# PSPS_AVNC_MITCH_2021-02-28.net
KiCad netlist of a schematic drawn in EAGLE
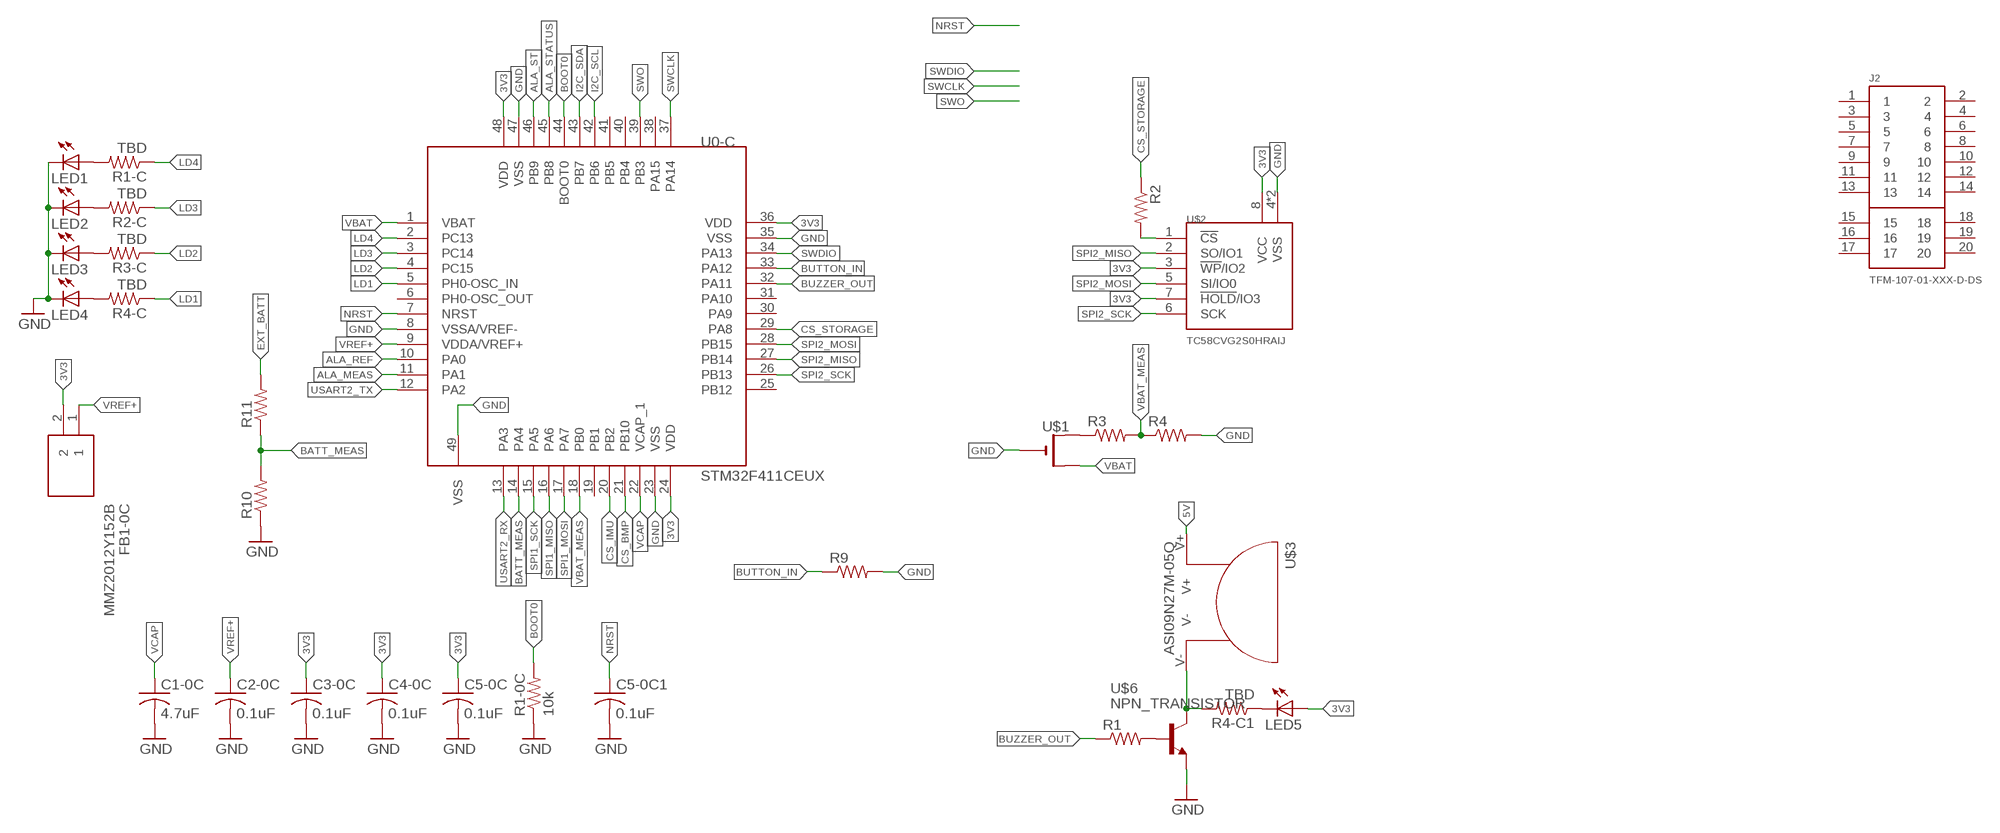
[diagram p0: schematic, sheet 1]
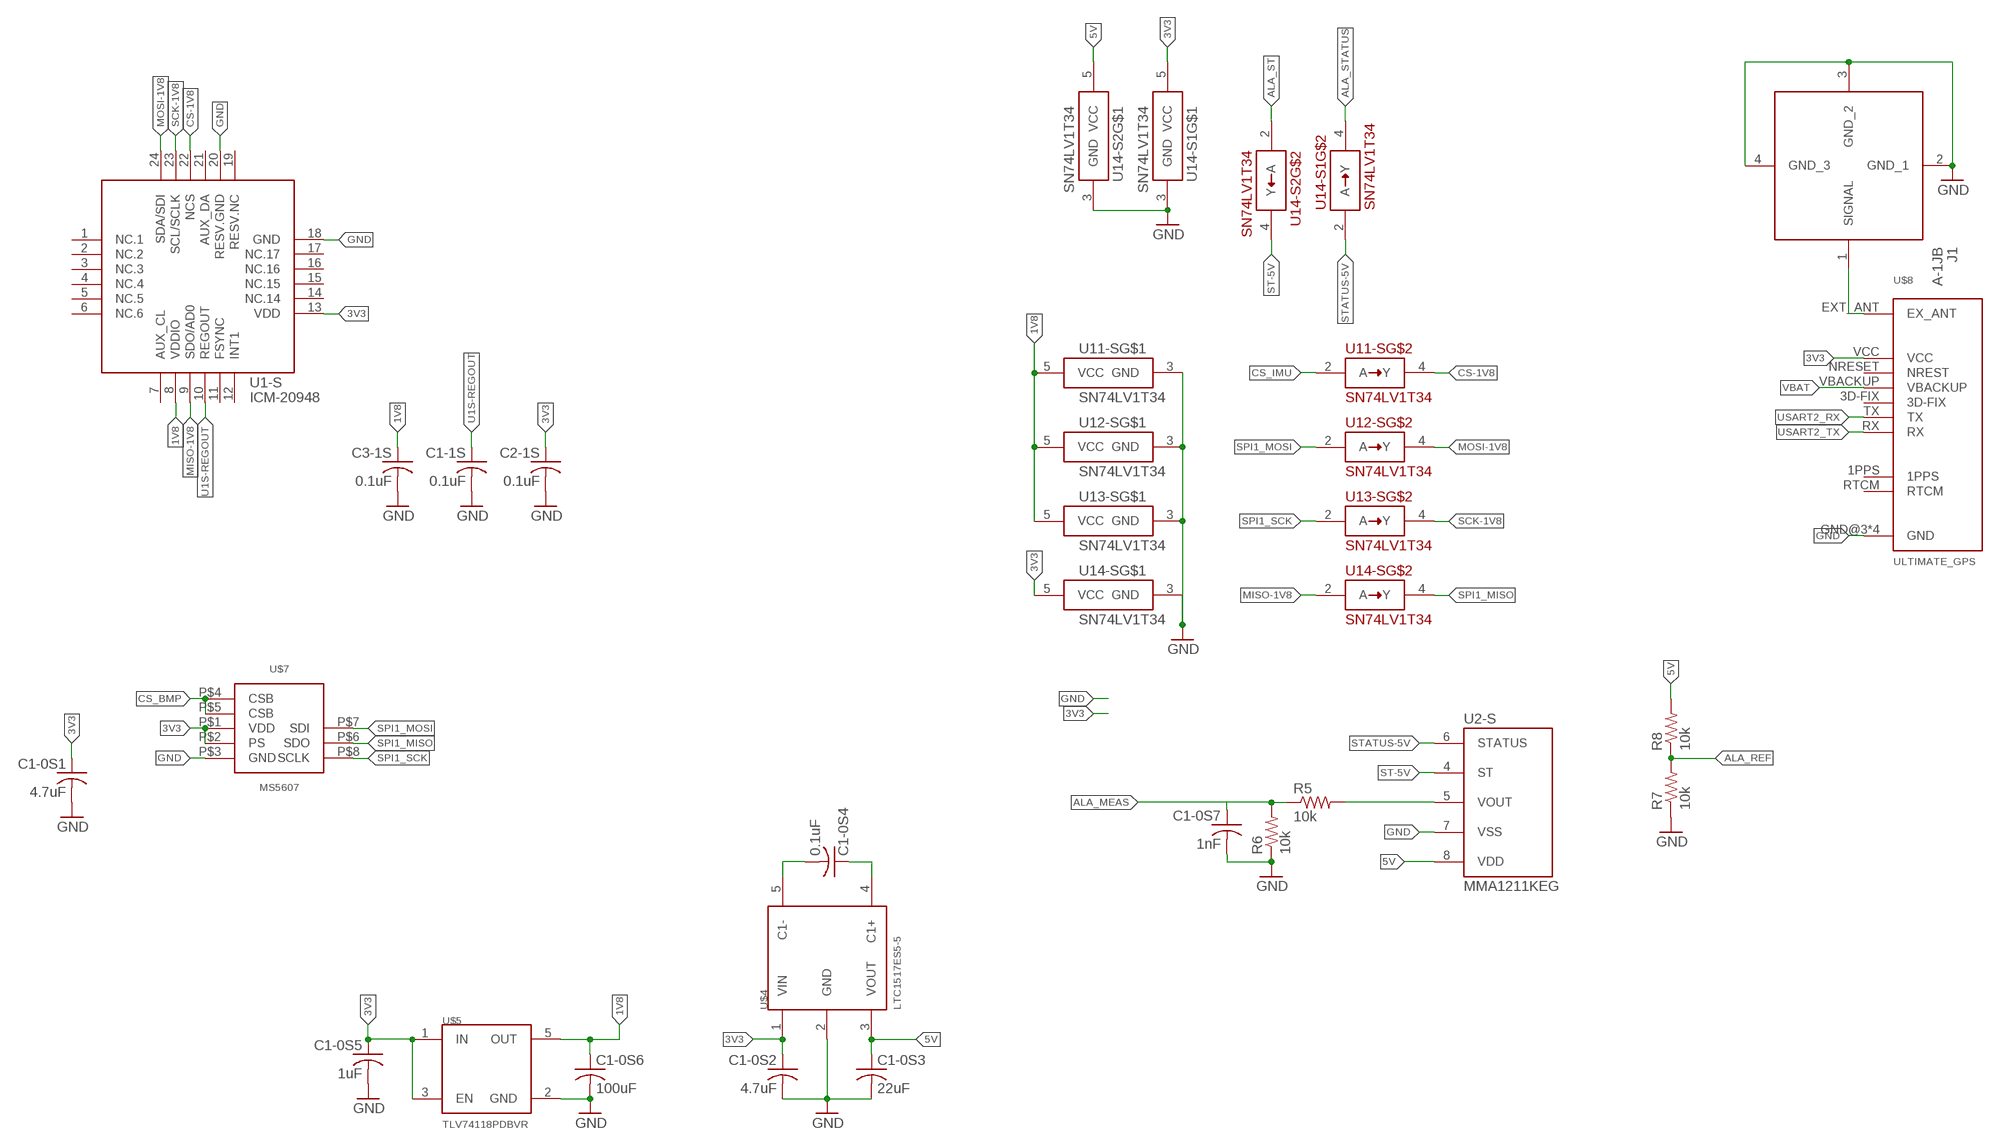
[diagram p1: schematic, sheet 2]

(export (version "E")
  (design (tool "Eeschema 10.0.6"))
  (components
    (comp (ref "C1-0C")
      (value "4.7uF")
      (footprint "eagle-import:C0805")
      (libsource (lib "eagle-import") (part "C-USC0805"))
    )
    (comp (ref "C2-0C")
      (value "0.1uF")
      (footprint "eagle-import:C0805")
      (libsource (lib "eagle-import") (part "C-USC0805"))
    )
    (comp (ref "C3-0C")
      (value "0.1uF")
      (footprint "eagle-import:C0805")
      (libsource (lib "eagle-import") (part "C-USC0805"))
    )
    (comp (ref "C4-0C")
      (value "0.1uF")
      (footprint "eagle-import:C0805")
      (libsource (lib "eagle-import") (part "C-USC0805"))
    )
    (comp (ref "C5-0C")
      (value "0.1uF")
      (footprint "eagle-import:C0805")
      (libsource (lib "eagle-import") (part "C-USC0805"))
    )
    (comp (ref "C5-0C1")
      (value "0.1uF")
      (footprint "eagle-import:C0805")
      (libsource (lib "eagle-import") (part "C-USC0805"))
    )
    (comp (ref "FB1-0C")
      (value "MMZ2012Y152B")
      (footprint "eagle-import:BEADC2012X105N")
      (fields (field (name "MOUSER_PART_NUMBER") "810-MMZ2012Y152B"))
      (libsource (lib "eagle-import") (part "MMZ2012Y152B"))
    )
    (comp (ref "J2")
      (value "TFM-107-01-XXX-D-DS")
      (footprint "eagle-import:TFM-107-01-XXX-D-DS")
      (libsource (lib "eagle-import") (part "TFM-107-01-XXX-D-DS"))
    )
    (comp (ref "LED1")
      (value "LEDCHIPLED_0805")
      (footprint "eagle-import:CHIPLED_0805")
      (libsource (lib "eagle-import") (part "LEDCHIPLED_0805"))
    )
    (comp (ref "LED2")
      (value "LEDCHIPLED_0805")
      (footprint "eagle-import:CHIPLED_0805")
      (libsource (lib "eagle-import") (part "LEDCHIPLED_0805"))
    )
    (comp (ref "LED3")
      (value "LEDCHIPLED_0805")
      (footprint "eagle-import:CHIPLED_0805")
      (libsource (lib "eagle-import") (part "LEDCHIPLED_0805"))
    )
    (comp (ref "LED4")
      (value "LEDCHIPLED_0805")
      (footprint "eagle-import:CHIPLED_0805")
      (libsource (lib "eagle-import") (part "LEDCHIPLED_0805"))
    )
    (comp (ref "LED5")
      (value "LEDCHIPLED_0805")
      (footprint "eagle-import:CHIPLED_0805")
      (libsource (lib "eagle-import") (part "LEDCHIPLED_0805"))
    )
    (comp (ref "R1")
      (value "R-US_R0805")
      (footprint "eagle-import:R0805")
      (libsource (lib "eagle-import") (part "R-US_R0805"))
    )
    (comp (ref "R1-0C")
      (value "10k")
      (footprint "eagle-import:R0805")
      (libsource (lib "eagle-import") (part "R-US_R0805"))
    )
    (comp (ref "R1-C")
      (value "TBD")
      (footprint "eagle-import:R0805")
      (libsource (lib "eagle-import") (part "R-US_R0805"))
    )
    (comp (ref "R2")
      (value "R-US_R0805")
      (footprint "eagle-import:R0805")
      (libsource (lib "eagle-import") (part "R-US_R0805"))
    )
    (comp (ref "R2-C")
      (value "TBD")
      (footprint "eagle-import:R0805")
      (libsource (lib "eagle-import") (part "R-US_R0805"))
    )
    (comp (ref "R3")
      (value "R-US_R0805")
      (footprint "eagle-import:R0805")
      (libsource (lib "eagle-import") (part "R-US_R0805"))
    )
    (comp (ref "R3-C")
      (value "TBD")
      (footprint "eagle-import:R0805")
      (libsource (lib "eagle-import") (part "R-US_R0805"))
    )
    (comp (ref "R4")
      (value "R-US_R0805")
      (footprint "eagle-import:R0805")
      (libsource (lib "eagle-import") (part "R-US_R0805"))
    )
    (comp (ref "R4-C")
      (value "TBD")
      (footprint "eagle-import:R0805")
      (libsource (lib "eagle-import") (part "R-US_R0805"))
    )
    (comp (ref "R4-C1")
      (value "TBD")
      (footprint "eagle-import:R0805")
      (libsource (lib "eagle-import") (part "R-US_R0805"))
    )
    (comp (ref "R9")
      (value "R-US_R0805")
      (footprint "eagle-import:R0805")
      (libsource (lib "eagle-import") (part "R-US_R0805"))
    )
    (comp (ref "R10")
      (value "R-US_R0805")
      (footprint "eagle-import:R0805")
      (libsource (lib "eagle-import") (part "R-US_R0805"))
    )
    (comp (ref "R11")
      (value "R-US_R0805")
      (footprint "eagle-import:R0805")
      (libsource (lib "eagle-import") (part "R-US_R0805"))
    )
    (comp (ref "U$1")
      (value "CR1220SMT")
      (footprint "eagle-import:CR1220-SMD")
      (libsource (lib "eagle-import") (part "CR1220SMT"))
    )
    (comp (ref "U$2")
      (value "TC58CVG2S0HRAIJ")
      (footprint "eagle-import:SON127P800X600X80-9T350X440N")
      (libsource (lib "eagle-import") (part "TC58CVG2S0HRAIJ"))
    )
    (comp (ref "U$3")
      (value "ASI09N27M-05Q")
      (footprint "eagle-import:ASI09N27M-05Q")
      (libsource (lib "eagle-import") (part "ASI09N27M-05Q"))
    )
    (comp (ref "U$6")
      (value "NPN_TRANSISTOR")
      (footprint "eagle-import:SOT23")
      (libsource (lib "eagle-import") (part "NPN_TRANSISTOR"))
    )
    (comp (ref "U0-C")
      (value "STM32F411CEUX")
      (footprint "eagle-import:QFN50P700X700X50-49T560N")
      (libsource (lib "eagle-import") (part "STM32F411CEUX"))
    )
    (comp (ref "C1-0S1")
      (value "4.7uF")
      (footprint "eagle-import:C0805")
      (libsource (lib "eagle-import") (part "C-USC0805"))
    )
    (comp (ref "C1-0S2")
      (value "4.7uF")
      (footprint "eagle-import:C0805")
      (libsource (lib "eagle-import") (part "C-USC0805"))
    )
    (comp (ref "C1-0S3")
      (value "22uF")
      (footprint "eagle-import:C0805")
      (libsource (lib "eagle-import") (part "C-USC0805"))
    )
    (comp (ref "C1-0S4")
      (value "0.1uF")
      (footprint "eagle-import:C0805")
      (libsource (lib "eagle-import") (part "C-USC0805"))
    )
    (comp (ref "C1-0S5")
      (value "1uF")
      (footprint "eagle-import:C0805")
      (libsource (lib "eagle-import") (part "C-USC0805"))
    )
    (comp (ref "C1-0S6")
      (value "100uF")
      (footprint "eagle-import:C0805")
      (libsource (lib "eagle-import") (part "C-USC0805"))
    )
    (comp (ref "C1-0S7")
      (value "1nF")
      (footprint "eagle-import:C0805")
      (libsource (lib "eagle-import") (part "C-USC0805"))
    )
    (comp (ref "C1-1S")
      (value "0.1uF")
      (footprint "eagle-import:C0805")
      (libsource (lib "eagle-import") (part "C-USC0805"))
    )
    (comp (ref "C2-1S")
      (value "0.1uF")
      (footprint "eagle-import:C0805")
      (libsource (lib "eagle-import") (part "C-USC0805"))
    )
    (comp (ref "C3-1S")
      (value "0.1uF")
      (footprint "eagle-import:C0805")
      (libsource (lib "eagle-import") (part "C-USC0805"))
    )
    (comp (ref "J1")
      (value "A-1JB")
      (footprint "eagle-import:A1JB")
      (fields (field (name "MOUSER_PART_NUMBER") "523-A-1JB"))
      (libsource (lib "eagle-import") (part "A-1JB"))
    )
    (comp (ref "R5")
      (value "10k")
      (footprint "eagle-import:R0805")
      (libsource (lib "eagle-import") (part "R-US_R0805"))
    )
    (comp (ref "R6")
      (value "10k")
      (footprint "eagle-import:R0805")
      (libsource (lib "eagle-import") (part "R-US_R0805"))
    )
    (comp (ref "R7")
      (value "10k")
      (footprint "eagle-import:R0805")
      (libsource (lib "eagle-import") (part "R-US_R0805"))
    )
    (comp (ref "R8")
      (value "10k")
      (footprint "eagle-import:R0805")
      (libsource (lib "eagle-import") (part "R-US_R0805"))
    )
    (comp (ref "U$4")
      (value "LTC1517ES5-5")
      (footprint "eagle-import:SOT95P280X145-5N")
      (libsource (lib "eagle-import") (part "LTC1517ES5-5"))
    )
    (comp (ref "U$5")
      (value "TLV74118PDBVR")
      (footprint "eagle-import:SOT95P280X145-5N")
      (libsource (lib "eagle-import") (part "TLV74118PDBVR"))
    )
    (comp (ref "U$7")
      (value "MS5607")
      (footprint "eagle-import:MS5607")
      (libsource (lib "eagle-import") (part "MS5607"))
    )
    (comp (ref "U$8")
      (value "ULTIMATE_GPS")
      (footprint "eagle-import:FGPMMOPA6H")
      (libsource (lib "eagle-import") (part "ULTIMATE_GPS"))
    )
    (comp (ref "U1-S")
      (value "ICM-20948")
      (footprint "eagle-import:QFN40P300X300X105-25T159X175")
      (libsource (lib "eagle-import") (part "ICM-20948"))
    )
    (comp (ref "U2-S")
      (value "MMA1211KEG")
      (footprint "eagle-import:SOIC127P1041X355-16N")
      (libsource (lib "eagle-import") (part "MMA1211KEG"))
    )
    (comp (ref "U11-S")
      (value "SN74LV1T34")
      (footprint "eagle-import:SOT65P210X110-5")
      (libsource (lib "eagle-import") (part "SN74LV1T34"))
    )
    (comp (ref "U12-S")
      (value "SN74LV1T34")
      (footprint "eagle-import:SOT65P210X110-5")
      (libsource (lib "eagle-import") (part "SN74LV1T34"))
    )
    (comp (ref "U13-S")
      (value "SN74LV1T34")
      (footprint "eagle-import:SOT65P210X110-5")
      (libsource (lib "eagle-import") (part "SN74LV1T34"))
    )
    (comp (ref "U14-S")
      (value "SN74LV1T34")
      (footprint "eagle-import:SOT65P210X110-5")
      (libsource (lib "eagle-import") (part "SN74LV1T34"))
    )
    (comp (ref "U14-S1")
      (value "SN74LV1T34")
      (footprint "eagle-import:SOT65P210X110-5")
      (libsource (lib "eagle-import") (part "SN74LV1T34"))
    )
    (comp (ref "U14-S2")
      (value "SN74LV1T34")
      (footprint "eagle-import:SOT65P210X110-5")
      (libsource (lib "eagle-import") (part "SN74LV1T34"))
    )
  )
  (nets
    (net (code "1") (name "1V8") (class "Default")
      (node (ref "C1-0S6") (pin "1") (pinfunction "1_1") (pintype "passive"))
      (node (ref "C3-1S") (pin "1") (pinfunction "1_1") (pintype "passive"))
      (node (ref "U$5") (pin "5") (pinfunction "OUT_5") (pintype "bidirectional"))
      (node (ref "U1-S") (pin "8") (pinfunction "VDDIO_8") (pintype "bidirectional"))
      (node (ref "U11-S") (pin "5") (pinfunction "VCC_5") (pintype "bidirectional"))
      (node (ref "U12-S") (pin "5") (pinfunction "VCC_5") (pintype "bidirectional"))
      (node (ref "U13-S") (pin "5") (pinfunction "VCC_5") (pintype "bidirectional"))
    )
    (net (code "2") (name "3V3") (class "Default")
      (node (ref "C1-0S1") (pin "1") (pinfunction "1_1") (pintype "passive"))
      (node (ref "C1-0S2") (pin "1") (pinfunction "1_1") (pintype "passive"))
      (node (ref "C1-0S5") (pin "1") (pinfunction "1_1") (pintype "passive"))
      (node (ref "C2-1S") (pin "1") (pinfunction "1_1") (pintype "passive"))
      (node (ref "C3-0C") (pin "1") (pinfunction "1_1") (pintype "passive"))
      (node (ref "C4-0C") (pin "1") (pinfunction "1_1") (pintype "passive"))
      (node (ref "C5-0C") (pin "1") (pinfunction "1_1") (pintype "passive"))
      (node (ref "FB1-0C") (pin "2") (pinfunction "2_2") (pintype "bidirectional"))
      (node (ref "LED5") (pin "A") (pinfunction "A_A") (pintype "passive"))
      (node (ref "U$2") (pin "3") (pinfunction "~{WP}/IO2_3") (pintype "bidirectional"))
      (node (ref "U$2") (pin "7") (pinfunction "~{HOLD}/IO3_7") (pintype "bidirectional"))
      (node (ref "U$2") (pin "8") (pinfunction "VCC_8") (pintype "bidirectional"))
      (node (ref "U$4") (pin "1") (pinfunction "VIN_1") (pintype "bidirectional"))
      (node (ref "U$5") (pin "1") (pinfunction "IN_1") (pintype "bidirectional"))
      (node (ref "U$5") (pin "3") (pinfunction "EN_3") (pintype "bidirectional"))
      (node (ref "U$7") (pin "P$1") (pinfunction "VDD_P$1") (pintype "bidirectional"))
      (node (ref "U$7") (pin "P$2") (pinfunction "PS_P$2") (pintype "bidirectional"))
      (node (ref "U$8") (pin "VCC") (pinfunction "VCC_VCC") (pintype "bidirectional"))
      (node (ref "U0-C") (pin "24") (pinfunction "VDD_24") (pintype "bidirectional"))
      (node (ref "U0-C") (pin "36") (pinfunction "VDD_36") (pintype "bidirectional"))
      (node (ref "U0-C") (pin "48") (pinfunction "VDD_48") (pintype "bidirectional"))
      (node (ref "U1-S") (pin "13") (pinfunction "VDD_13") (pintype "bidirectional"))
      (node (ref "U14-S") (pin "5") (pinfunction "VCC_5") (pintype "bidirectional"))
      (node (ref "U14-S1") (pin "5") (pinfunction "VCC_5") (pintype "bidirectional"))
    )
    (net (code "3") (name "5V") (class "Default")
      (node (ref "C1-0S3") (pin "1") (pinfunction "1_1") (pintype "passive"))
      (node (ref "R8") (pin "2") (pinfunction "2_2") (pintype "passive"))
      (node (ref "U$3") (pin "V+") (pinfunction "V+_V+") (pintype "bidirectional"))
      (node (ref "U$4") (pin "3") (pinfunction "VOUT_3") (pintype "bidirectional"))
      (node (ref "U14-S2") (pin "5") (pinfunction "VCC_5") (pintype "bidirectional"))
      (node (ref "U2-S") (pin "8") (pinfunction "VDD_8") (pintype "bidirectional"))
    )
    (net (code "4") (name "ALA_MEAS") (class "Default")
      (node (ref "C1-0S7") (pin "1") (pinfunction "1_1") (pintype "passive"))
      (node (ref "R5") (pin "1") (pinfunction "1_1") (pintype "passive"))
      (node (ref "R6") (pin "2") (pinfunction "2_2") (pintype "passive"))
      (node (ref "U0-C") (pin "11") (pinfunction "PA1_11") (pintype "bidirectional"))
    )
    (net (code "5") (name "ALA_REF") (class "Default")
      (node (ref "R7") (pin "2") (pinfunction "2_2") (pintype "passive"))
      (node (ref "R8") (pin "1") (pinfunction "1_1") (pintype "passive"))
      (node (ref "U0-C") (pin "10") (pinfunction "PA0_10") (pintype "bidirectional"))
    )
    (net (code "6") (name "ALA_ST") (class "Default")
      (node (ref "U0-C") (pin "46") (pinfunction "PB9_46") (pintype "bidirectional"))
      (node (ref "U14-S2") (pin "2") (pinfunction "A_2") (pintype "bidirectional"))
    )
    (net (code "7") (name "ALA_STATUS") (class "Default")
      (node (ref "U0-C") (pin "45") (pinfunction "PB8_45") (pintype "bidirectional"))
      (node (ref "U14-S1") (pin "4") (pinfunction "Y_4") (pintype "bidirectional"))
    )
    (net (code "8") (name "BATT_MEAS") (class "Default")
      (node (ref "R10") (pin "2") (pinfunction "2_2") (pintype "passive"))
      (node (ref "R11") (pin "1") (pinfunction "1_1") (pintype "passive"))
      (node (ref "U0-C") (pin "14") (pinfunction "PA4_14") (pintype "bidirectional"))
    )
    (net (code "9") (name "BOOT0") (class "Default")
      (node (ref "R1-0C") (pin "2") (pinfunction "2_2") (pintype "passive"))
      (node (ref "U0-C") (pin "44") (pinfunction "BOOT0_44") (pintype "bidirectional"))
    )
    (net (code "10") (name "BUTTON_IN") (class "Default")
      (node (ref "R9") (pin "1") (pinfunction "1_1") (pintype "passive"))
      (node (ref "U0-C") (pin "33") (pinfunction "PA12_33") (pintype "bidirectional"))
    )
    (net (code "11") (name "BUZZER_OUT") (class "Default")
      (node (ref "R1") (pin "1") (pinfunction "1_1") (pintype "passive"))
      (node (ref "U0-C") (pin "32") (pinfunction "PA11_32") (pintype "bidirectional"))
    )
    (net (code "12") (name "CS-1V8") (class "Default")
      (node (ref "U1-S") (pin "22") (pinfunction "NCS_22") (pintype "bidirectional"))
      (node (ref "U11-S") (pin "4") (pinfunction "Y_4") (pintype "bidirectional"))
    )
    (net (code "13") (name "CS_BMP") (class "Default")
      (node (ref "U$7") (pin "P$4") (pinfunction "CSB_P$4") (pintype "bidirectional"))
      (node (ref "U$7") (pin "P$5") (pinfunction "CSB_P$5") (pintype "bidirectional"))
      (node (ref "U0-C") (pin "21") (pinfunction "PB10_21") (pintype "bidirectional"))
    )
    (net (code "14") (name "CS_IMU") (class "Default")
      (node (ref "U0-C") (pin "20") (pinfunction "PB2_20") (pintype "bidirectional"))
      (node (ref "U11-S") (pin "2") (pinfunction "A_2") (pintype "bidirectional"))
    )
    (net (code "15") (name "CS_STORAGE") (class "Default")
      (node (ref "R2") (pin "1") (pinfunction "1_1") (pintype "passive"))
      (node (ref "U0-C") (pin "29") (pinfunction "PA8_29") (pintype "bidirectional"))
    )
    (net (code "16") (name "EXT_BATT") (class "Default")
      (node (ref "R11") (pin "2") (pinfunction "2_2") (pintype "passive"))
    )
    (net (code "17") (name "GND") (class "Default")
      (node (ref "C1-0C") (pin "2") (pinfunction "2_2") (pintype "passive"))
      (node (ref "C1-0S1") (pin "2") (pinfunction "2_2") (pintype "passive"))
      (node (ref "C1-0S2") (pin "2") (pinfunction "2_2") (pintype "passive"))
      (node (ref "C1-0S3") (pin "2") (pinfunction "2_2") (pintype "passive"))
      (node (ref "C1-0S5") (pin "2") (pinfunction "2_2") (pintype "passive"))
      (node (ref "C1-0S6") (pin "2") (pinfunction "2_2") (pintype "passive"))
      (node (ref "C1-0S7") (pin "2") (pinfunction "2_2") (pintype "passive"))
      (node (ref "C1-1S") (pin "2") (pinfunction "2_2") (pintype "passive"))
      (node (ref "C2-0C") (pin "2") (pinfunction "2_2") (pintype "passive"))
      (node (ref "C2-1S") (pin "2") (pinfunction "2_2") (pintype "passive"))
      (node (ref "C3-0C") (pin "2") (pinfunction "2_2") (pintype "passive"))
      (node (ref "C3-1S") (pin "2") (pinfunction "2_2") (pintype "passive"))
      (node (ref "C4-0C") (pin "2") (pinfunction "2_2") (pintype "passive"))
      (node (ref "C5-0C") (pin "2") (pinfunction "2_2") (pintype "passive"))
      (node (ref "C5-0C1") (pin "2") (pinfunction "2_2") (pintype "passive"))
      (node (ref "J1") (pin "2") (pinfunction "GND_1_2") (pintype "bidirectional"))
      (node (ref "J1") (pin "3") (pinfunction "GND_2_3") (pintype "bidirectional"))
      (node (ref "J1") (pin "4") (pinfunction "GND_3_4") (pintype "bidirectional"))
      (node (ref "LED1") (pin "C") (pinfunction "C_C") (pintype "passive"))
      (node (ref "LED2") (pin "C") (pinfunction "C_C") (pintype "passive"))
      (node (ref "LED3") (pin "C") (pinfunction "C_C") (pintype "passive"))
      (node (ref "LED4") (pin "C") (pinfunction "C_C") (pintype "passive"))
      (node (ref "R1-0C") (pin "1") (pinfunction "1_1") (pintype "passive"))
      (node (ref "R10") (pin "1") (pinfunction "1_1") (pintype "passive"))
      (node (ref "R4") (pin "2") (pinfunction "2_2") (pintype "passive"))
      (node (ref "R6") (pin "1") (pinfunction "1_1") (pintype "passive"))
      (node (ref "R7") (pin "1") (pinfunction "1_1") (pintype "passive"))
      (node (ref "R9") (pin "2") (pinfunction "2_2") (pintype "passive"))
      (node (ref "U$1") (pin "-") (pinfunction "-_-") (pintype "passive"))
      (node (ref "U$2") (pin "4") (pinfunction "VSS_4") (pintype "bidirectional"))
      (node (ref "U$2") (pin "9") (pinfunction "VSS_9") (pintype "bidirectional"))
      (node (ref "U$4") (pin "2") (pinfunction "GND_2") (pintype "bidirectional"))
      (node (ref "U$5") (pin "2") (pinfunction "GND_2") (pintype "bidirectional"))
      (node (ref "U$6") (pin "3") (pinfunction "E_3") (pintype "passive"))
      (node (ref "U$7") (pin "P$3") (pinfunction "GND_P$3") (pintype "bidirectional"))
      (node (ref "U$8") (pin "GND@12") (pinfunction "GND_GND@12") (pintype "bidirectional"))
      (node (ref "U$8") (pin "GND@19") (pinfunction "GND_GND@19") (pintype "bidirectional"))
      (node (ref "U$8") (pin "GND@3") (pinfunction "GND_GND@3") (pintype "bidirectional"))
      (node (ref "U$8") (pin "GND@8") (pinfunction "GND_GND@8") (pintype "bidirectional"))
      (node (ref "U0-C") (pin "23") (pinfunction "VSS_23") (pintype "bidirectional"))
      (node (ref "U0-C") (pin "35") (pinfunction "VSS_35") (pintype "bidirectional"))
      (node (ref "U0-C") (pin "47") (pinfunction "VSS_47") (pintype "bidirectional"))
      (node (ref "U0-C") (pin "49") (pinfunction "VSS_49") (pintype "bidirectional"))
      (node (ref "U0-C") (pin "8") (pinfunction "VSSA/VREF-_8") (pintype "bidirectional"))
      (node (ref "U1-S") (pin "18") (pinfunction "GND_18") (pintype "bidirectional"))
      (node (ref "U1-S") (pin "20") (pinfunction "RESV.GND_20") (pintype "bidirectional"))
      (node (ref "U11-S") (pin "3") (pinfunction "GND_3") (pintype "bidirectional"))
      (node (ref "U12-S") (pin "3") (pinfunction "GND_3") (pintype "bidirectional"))
      (node (ref "U13-S") (pin "3") (pinfunction "GND_3") (pintype "bidirectional"))
      (node (ref "U14-S") (pin "3") (pinfunction "GND_3") (pintype "bidirectional"))
      (node (ref "U14-S1") (pin "3") (pinfunction "GND_3") (pintype "bidirectional"))
      (node (ref "U14-S2") (pin "3") (pinfunction "GND_3") (pintype "bidirectional"))
      (node (ref "U2-S") (pin "7") (pinfunction "VSS_7") (pintype "bidirectional"))
    )
    (net (code "18") (name "I2C_SCL") (class "Default")
      (node (ref "U0-C") (pin "42") (pinfunction "PB6_42") (pintype "bidirectional"))
    )
    (net (code "19") (name "I2C_SDA") (class "Default")
      (node (ref "U0-C") (pin "43") (pinfunction "PB7_43") (pintype "bidirectional"))
    )
    (net (code "20") (name "LD1") (class "Default")
      (node (ref "R4-C") (pin "1") (pinfunction "1_1") (pintype "passive"))
      (node (ref "U0-C") (pin "5") (pinfunction "PH0-OSC_IN_5") (pintype "bidirectional"))
    )
    (net (code "21") (name "LD2") (class "Default")
      (node (ref "R3-C") (pin "1") (pinfunction "1_1") (pintype "passive"))
      (node (ref "U0-C") (pin "4") (pinfunction "PC15_4") (pintype "bidirectional"))
    )
    (net (code "22") (name "LD3") (class "Default")
      (node (ref "R2-C") (pin "1") (pinfunction "1_1") (pintype "passive"))
      (node (ref "U0-C") (pin "3") (pinfunction "PC14_3") (pintype "bidirectional"))
    )
    (net (code "23") (name "LD4") (class "Default")
      (node (ref "R1-C") (pin "1") (pinfunction "1_1") (pintype "passive"))
      (node (ref "U0-C") (pin "2") (pinfunction "PC13_2") (pintype "bidirectional"))
    )
    (net (code "24") (name "MISO-1V8") (class "Default")
      (node (ref "U1-S") (pin "9") (pinfunction "SDO/AD0_9") (pintype "bidirectional"))
      (node (ref "U14-S") (pin "2") (pinfunction "A_2") (pintype "bidirectional"))
    )
    (net (code "25") (name "MOSI-1V8") (class "Default")
      (node (ref "U1-S") (pin "24") (pinfunction "SDA/SDI_24") (pintype "bidirectional"))
      (node (ref "U12-S") (pin "4") (pinfunction "Y_4") (pintype "bidirectional"))
    )
    (net (code "26") (name "NRST") (class "Default")
      (node (ref "C5-0C1") (pin "1") (pinfunction "1_1") (pintype "passive"))
      (node (ref "U0-C") (pin "7") (pinfunction "NRST_7") (pintype "bidirectional"))
    )
    (net (code "27") (name "Net-(J1-SIGNAL)") (class "Default")
      (node (ref "J1") (pin "1") (pinfunction "SIGNAL_1") (pintype "bidirectional"))
      (node (ref "U$8") (pin "EXT_ANT") (pinfunction "EX_ANT_EXT_ANT") (pintype "bidirectional"))
    )
    (net (code "28") (name "Net-(LED1-PadA)") (class "Default")
      (node (ref "LED1") (pin "A") (pinfunction "A_A") (pintype "passive"))
      (node (ref "R1-C") (pin "2") (pinfunction "2_2") (pintype "passive"))
    )
    (net (code "29") (name "Net-(LED2-PadA)") (class "Default")
      (node (ref "LED2") (pin "A") (pinfunction "A_A") (pintype "passive"))
      (node (ref "R2-C") (pin "2") (pinfunction "2_2") (pintype "passive"))
    )
    (net (code "30") (name "Net-(LED3-PadA)") (class "Default")
      (node (ref "LED3") (pin "A") (pinfunction "A_A") (pintype "passive"))
      (node (ref "R3-C") (pin "2") (pinfunction "2_2") (pintype "passive"))
    )
    (net (code "31") (name "Net-(LED4-PadA)") (class "Default")
      (node (ref "LED4") (pin "A") (pinfunction "A_A") (pintype "passive"))
      (node (ref "R4-C") (pin "2") (pinfunction "2_2") (pintype "passive"))
    )
    (net (code "32") (name "Net-(LED5-PadC)") (class "Default")
      (node (ref "LED5") (pin "C") (pinfunction "C_C") (pintype "passive"))
      (node (ref "R4-C1") (pin "1") (pinfunction "1_1") (pintype "passive"))
    )
    (net (code "33") (name "Net-(U$1-+)") (class "Default")
      (node (ref "R3") (pin "1") (pinfunction "1_1") (pintype "passive"))
      (node (ref "U$1") (pin "+$1") (pinfunction "+_+$1") (pintype "passive"))
    )
    (net (code "34") (name "Net-(U$2-~{CS})") (class "Default")
      (node (ref "R2") (pin "2") (pinfunction "2_2") (pintype "passive"))
      (node (ref "U$2") (pin "1") (pinfunction "~{CS}_1") (pintype "bidirectional"))
    )
    (net (code "35") (name "Net-(U$4-C1+)") (class "Default")
      (node (ref "C1-0S4") (pin "1") (pinfunction "1_1") (pintype "passive"))
      (node (ref "U$4") (pin "4") (pinfunction "C1+_4") (pintype "bidirectional"))
    )
    (net (code "36") (name "Net-(U$4-C1-)") (class "Default")
      (node (ref "C1-0S4") (pin "2") (pinfunction "2_2") (pintype "passive"))
      (node (ref "U$4") (pin "5") (pinfunction "C1-_5") (pintype "bidirectional"))
    )
    (net (code "37") (name "Net-(U$6-B)") (class "Default")
      (node (ref "R1") (pin "2") (pinfunction "2_2") (pintype "passive"))
      (node (ref "U$6") (pin "1") (pinfunction "B_1") (pintype "passive"))
    )
    (net (code "38") (name "Net-(U$6-C)") (class "Default")
      (node (ref "R4-C1") (pin "2") (pinfunction "2_2") (pintype "passive"))
      (node (ref "U$3") (pin "V-") (pinfunction "V-_V-") (pintype "bidirectional"))
      (node (ref "U$6") (pin "2") (pinfunction "C_2") (pintype "passive"))
    )
    (net (code "39") (name "Net-(U2-S-VOUT)") (class "Default")
      (node (ref "R5") (pin "2") (pinfunction "2_2") (pintype "passive"))
      (node (ref "U2-S") (pin "5") (pinfunction "VOUT_5") (pintype "bidirectional"))
    )
    (net (code "40") (name "SCK-1V8") (class "Default")
      (node (ref "U1-S") (pin "23") (pinfunction "SCL/SCLK_23") (pintype "bidirectional"))
      (node (ref "U13-S") (pin "4") (pinfunction "Y_4") (pintype "bidirectional"))
    )
    (net (code "41") (name "SPI1_MISO") (class "Default")
      (node (ref "U$7") (pin "P$6") (pinfunction "SDO_P$6") (pintype "bidirectional"))
      (node (ref "U0-C") (pin "16") (pinfunction "PA6_16") (pintype "bidirectional"))
      (node (ref "U14-S") (pin "4") (pinfunction "Y_4") (pintype "bidirectional"))
    )
    (net (code "42") (name "SPI1_MOSI") (class "Default")
      (node (ref "U$7") (pin "P$7") (pinfunction "SDI_P$7") (pintype "bidirectional"))
      (node (ref "U0-C") (pin "17") (pinfunction "PA7_17") (pintype "bidirectional"))
      (node (ref "U12-S") (pin "2") (pinfunction "A_2") (pintype "bidirectional"))
    )
    (net (code "43") (name "SPI1_SCK") (class "Default")
      (node (ref "U$7") (pin "P$8") (pinfunction "SCLK_P$8") (pintype "bidirectional"))
      (node (ref "U0-C") (pin "15") (pinfunction "PA5_15") (pintype "bidirectional"))
      (node (ref "U13-S") (pin "2") (pinfunction "A_2") (pintype "bidirectional"))
    )
    (net (code "44") (name "SPI2_MISO") (class "Default")
      (node (ref "U$2") (pin "2") (pinfunction "SO/IO1_2") (pintype "bidirectional"))
      (node (ref "U0-C") (pin "27") (pinfunction "PB14_27") (pintype "bidirectional"))
    )
    (net (code "45") (name "SPI2_MOSI") (class "Default")
      (node (ref "U$2") (pin "5") (pinfunction "SI/IO0_5") (pintype "bidirectional"))
      (node (ref "U0-C") (pin "28") (pinfunction "PB15_28") (pintype "bidirectional"))
    )
    (net (code "46") (name "SPI2_SCK") (class "Default")
      (node (ref "U$2") (pin "6") (pinfunction "SCK_6") (pintype "bidirectional"))
      (node (ref "U0-C") (pin "26") (pinfunction "PB13_26") (pintype "bidirectional"))
    )
    (net (code "47") (name "ST-5V") (class "Default")
      (node (ref "U14-S2") (pin "4") (pinfunction "Y_4") (pintype "bidirectional"))
      (node (ref "U2-S") (pin "4") (pinfunction "ST_4") (pintype "bidirectional"))
    )
    (net (code "48") (name "STATUS-5V") (class "Default")
      (node (ref "U14-S1") (pin "2") (pinfunction "A_2") (pintype "bidirectional"))
      (node (ref "U2-S") (pin "6") (pinfunction "STATUS_6") (pintype "bidirectional"))
    )
    (net (code "49") (name "SWCLK") (class "Default")
      (node (ref "U0-C") (pin "37") (pinfunction "PA14_37") (pintype "bidirectional"))
    )
    (net (code "50") (name "SWDIO") (class "Default")
      (node (ref "U0-C") (pin "34") (pinfunction "PA13_34") (pintype "bidirectional"))
    )
    (net (code "51") (name "SWO") (class "Default")
      (node (ref "U0-C") (pin "39") (pinfunction "PB3_39") (pintype "bidirectional"))
    )
    (net (code "52") (name "U1S-REGOUT") (class "Default")
      (node (ref "C1-1S") (pin "1") (pinfunction "1_1") (pintype "passive"))
      (node (ref "U1-S") (pin "10") (pinfunction "REGOUT_10") (pintype "bidirectional"))
    )
    (net (code "53") (name "USART2_RX") (class "Default")
      (node (ref "U$8") (pin "TX") (pinfunction "TX_TX") (pintype "bidirectional"))
      (node (ref "U0-C") (pin "13") (pinfunction "PA3_13") (pintype "bidirectional"))
    )
    (net (code "54") (name "USART2_TX") (class "Default")
      (node (ref "U$8") (pin "RX") (pinfunction "RX_RX") (pintype "bidirectional"))
      (node (ref "U0-C") (pin "12") (pinfunction "PA2_12") (pintype "bidirectional"))
    )
    (net (code "55") (name "VBAT") (class "Default")
      (node (ref "U$1") (pin "+$2") (pinfunction "+1_+$2") (pintype "passive"))
      (node (ref "U$8") (pin "VBACKUP") (pinfunction "VBACKUP_VBACKUP") (pintype "bidirectional"))
      (node (ref "U0-C") (pin "1") (pinfunction "VBAT_1") (pintype "bidirectional"))
    )
    (net (code "56") (name "VBAT_MEAS") (class "Default")
      (node (ref "R3") (pin "2") (pinfunction "2_2") (pintype "passive"))
      (node (ref "R4") (pin "1") (pinfunction "1_1") (pintype "passive"))
      (node (ref "U0-C") (pin "18") (pinfunction "PB0_18") (pintype "bidirectional"))
    )
    (net (code "57") (name "VCAP") (class "Default")
      (node (ref "C1-0C") (pin "1") (pinfunction "1_1") (pintype "passive"))
      (node (ref "U0-C") (pin "22") (pinfunction "VCAP_1_22") (pintype "bidirectional"))
    )
    (net (code "58") (name "VREF+") (class "Default")
      (node (ref "C2-0C") (pin "1") (pinfunction "1_1") (pintype "passive"))
      (node (ref "FB1-0C") (pin "1") (pinfunction "1_1") (pintype "bidirectional"))
      (node (ref "U0-C") (pin "9") (pinfunction "VDDA/VREF+_9") (pintype "bidirectional"))
    )
    (net (code "59") (name "unconnected-(J2-Pad1)") (class "Default")
      (node (ref "J2") (pin "1") (pinfunction "1_1") (pintype "bidirectional"))
    )
    (net (code "60") (name "unconnected-(J2-Pad2)") (class "Default")
      (node (ref "J2") (pin "2") (pinfunction "2_2") (pintype "bidirectional"))
    )
    (net (code "61") (name "unconnected-(J2-Pad3)") (class "Default")
      (node (ref "J2") (pin "3") (pinfunction "3_3") (pintype "bidirectional"))
    )
    (net (code "62") (name "unconnected-(J2-Pad4)") (class "Default")
      (node (ref "J2") (pin "4") (pinfunction "4_4") (pintype "bidirectional"))
    )
    (net (code "63") (name "unconnected-(J2-Pad5)") (class "Default")
      (node (ref "J2") (pin "5") (pinfunction "5_5") (pintype "bidirectional"))
    )
    (net (code "64") (name "unconnected-(J2-Pad6)") (class "Default")
      (node (ref "J2") (pin "6") (pinfunction "6_6") (pintype "bidirectional"))
    )
    (net (code "65") (name "unconnected-(J2-Pad7)") (class "Default")
      (node (ref "J2") (pin "7") (pinfunction "7_7") (pintype "bidirectional"))
    )
    (net (code "66") (name "unconnected-(J2-Pad8)") (class "Default")
      (node (ref "J2") (pin "8") (pinfunction "8_8") (pintype "bidirectional"))
    )
    (net (code "67") (name "unconnected-(J2-Pad9)") (class "Default")
      (node (ref "J2") (pin "9") (pinfunction "9_9") (pintype "bidirectional"))
    )
    (net (code "68") (name "unconnected-(J2-Pad10)") (class "Default")
      (node (ref "J2") (pin "10") (pinfunction "10_10") (pintype "bidirectional"))
    )
    (net (code "69") (name "unconnected-(J2-Pad11)") (class "Default")
      (node (ref "J2") (pin "11") (pinfunction "11_11") (pintype "bidirectional"))
    )
    (net (code "70") (name "unconnected-(J2-Pad12)") (class "Default")
      (node (ref "J2") (pin "12") (pinfunction "12_12") (pintype "bidirectional"))
    )
    (net (code "71") (name "unconnected-(J2-Pad13)") (class "Default")
      (node (ref "J2") (pin "13") (pinfunction "13_13") (pintype "bidirectional"))
    )
    (net (code "72") (name "unconnected-(J2-Pad14)") (class "Default")
      (node (ref "J2") (pin "14") (pinfunction "14_14") (pintype "bidirectional"))
    )
    (net (code "73") (name "unconnected-(J2-Pad15)") (class "Default")
      (node (ref "J2") (pin "15") (pinfunction "15_15") (pintype "bidirectional"))
    )
    (net (code "74") (name "unconnected-(J2-Pad16)") (class "Default")
      (node (ref "J2") (pin "16") (pinfunction "16_16") (pintype "bidirectional"))
    )
    (net (code "75") (name "unconnected-(J2-Pad17)") (class "Default")
      (node (ref "J2") (pin "17") (pinfunction "17_17") (pintype "bidirectional"))
    )
    (net (code "76") (name "unconnected-(J2-Pad18)") (class "Default")
      (node (ref "J2") (pin "18") (pinfunction "18_18") (pintype "bidirectional"))
    )
    (net (code "77") (name "unconnected-(J2-Pad19)") (class "Default")
      (node (ref "J2") (pin "19") (pinfunction "19_19") (pintype "bidirectional"))
    )
    (net (code "78") (name "unconnected-(J2-Pad20)") (class "Default")
      (node (ref "J2") (pin "20") (pinfunction "20_20") (pintype "bidirectional"))
    )
    (net (code "79") (name "unconnected-(U$8-NREST-PadNRESET)") (class "Default")
      (node (ref "U$8") (pin "NRESET") (pinfunction "NREST_NRESET") (pintype "bidirectional"))
    )
    (net (code "80") (name "unconnected-(U$8-Pad1PPS)") (class "Default")
      (node (ref "U$8") (pin "1PPS") (pinfunction "1PPS_1PPS") (pintype "bidirectional"))
    )
    (net (code "81") (name "unconnected-(U$8-Pad3D-FIX)") (class "Default")
      (node (ref "U$8") (pin "3D-FIX") (pinfunction "3D-FIX_3D-FIX") (pintype "bidirectional"))
    )
    (net (code "82") (name "unconnected-(U$8-PadRTCM)") (class "Default")
      (node (ref "U$8") (pin "RTCM") (pinfunction "RTCM_RTCM") (pintype "bidirectional"))
    )
    (net (code "83") (name "unconnected-(U0-C-PA9-Pad30)") (class "Default")
      (node (ref "U0-C") (pin "30") (pinfunction "PA9_30") (pintype "bidirectional"))
    )
    (net (code "84") (name "unconnected-(U0-C-PA10-Pad31)") (class "Default")
      (node (ref "U0-C") (pin "31") (pinfunction "PA10_31") (pintype "bidirectional"))
    )
    (net (code "85") (name "unconnected-(U0-C-PA15-Pad38)") (class "Default")
      (node (ref "U0-C") (pin "38") (pinfunction "PA15_38") (pintype "bidirectional"))
    )
    (net (code "86") (name "unconnected-(U0-C-PB1-Pad19)") (class "Default")
      (node (ref "U0-C") (pin "19") (pinfunction "PB1_19") (pintype "bidirectional"))
    )
    (net (code "87") (name "unconnected-(U0-C-PB4-Pad40)") (class "Default")
      (node (ref "U0-C") (pin "40") (pinfunction "PB4_40") (pintype "bidirectional"))
    )
    (net (code "88") (name "unconnected-(U0-C-PB5-Pad41)") (class "Default")
      (node (ref "U0-C") (pin "41") (pinfunction "PB5_41") (pintype "bidirectional"))
    )
    (net (code "89") (name "unconnected-(U0-C-PB12-Pad25)") (class "Default")
      (node (ref "U0-C") (pin "25") (pinfunction "PB12_25") (pintype "bidirectional"))
    )
    (net (code "90") (name "unconnected-(U0-C-PH0-OSC_OUT-Pad6)") (class "Default")
      (node (ref "U0-C") (pin "6") (pinfunction "PH0-OSC_OUT_6") (pintype "bidirectional"))
    )
    (net (code "91") (name "unconnected-(U1-S-AUX_CL-Pad7)") (class "Default")
      (node (ref "U1-S") (pin "7") (pinfunction "AUX_CL_7") (pintype "bidirectional"))
    )
    (net (code "92") (name "unconnected-(U1-S-AUX_DA-Pad21)") (class "Default")
      (node (ref "U1-S") (pin "21") (pinfunction "AUX_DA_21") (pintype "bidirectional"))
    )
    (net (code "93") (name "unconnected-(U1-S-FSYNC-Pad11)") (class "Default")
      (node (ref "U1-S") (pin "11") (pinfunction "FSYNC_11") (pintype "bidirectional"))
    )
    (net (code "94") (name "unconnected-(U1-S-INT1-Pad12)") (class "Default")
      (node (ref "U1-S") (pin "12") (pinfunction "INT1_12") (pintype "bidirectional"))
    )
    (net (code "95") (name "unconnected-(U1-S-NC.1-Pad1)") (class "Default")
      (node (ref "U1-S") (pin "1") (pinfunction "NC.1_1") (pintype "bidirectional"))
    )
    (net (code "96") (name "unconnected-(U1-S-NC.2-Pad2)") (class "Default")
      (node (ref "U1-S") (pin "2") (pinfunction "NC.2_2") (pintype "bidirectional"))
    )
    (net (code "97") (name "unconnected-(U1-S-NC.3-Pad3)") (class "Default")
      (node (ref "U1-S") (pin "3") (pinfunction "NC.3_3") (pintype "bidirectional"))
    )
    (net (code "98") (name "unconnected-(U1-S-NC.4-Pad4)") (class "Default")
      (node (ref "U1-S") (pin "4") (pinfunction "NC.4_4") (pintype "bidirectional"))
    )
    (net (code "99") (name "unconnected-(U1-S-NC.5-Pad5)") (class "Default")
      (node (ref "U1-S") (pin "5") (pinfunction "NC.5_5") (pintype "bidirectional"))
    )
    (net (code "100") (name "unconnected-(U1-S-NC.6-Pad6)") (class "Default")
      (node (ref "U1-S") (pin "6") (pinfunction "NC.6_6") (pintype "bidirectional"))
    )
    (net (code "101") (name "unconnected-(U1-S-NC.14-Pad14)") (class "Default")
      (node (ref "U1-S") (pin "14") (pinfunction "NC.14_14") (pintype "bidirectional"))
    )
    (net (code "102") (name "unconnected-(U1-S-NC.15-Pad15)") (class "Default")
      (node (ref "U1-S") (pin "15") (pinfunction "NC.15_15") (pintype "bidirectional"))
    )
    (net (code "103") (name "unconnected-(U1-S-NC.16-Pad16)") (class "Default")
      (node (ref "U1-S") (pin "16") (pinfunction "NC.16_16") (pintype "bidirectional"))
    )
    (net (code "104") (name "unconnected-(U1-S-NC.17-Pad17)") (class "Default")
      (node (ref "U1-S") (pin "17") (pinfunction "NC.17_17") (pintype "bidirectional"))
    )
    (net (code "105") (name "unconnected-(U1-S-RESV.NC-Pad19)") (class "Default")
      (node (ref "U1-S") (pin "19") (pinfunction "RESV.NC_19") (pintype "bidirectional"))
    )
  )
)
